# TI_DAC5V.net
KiCad netlist of a schematic drawn in EAGLE
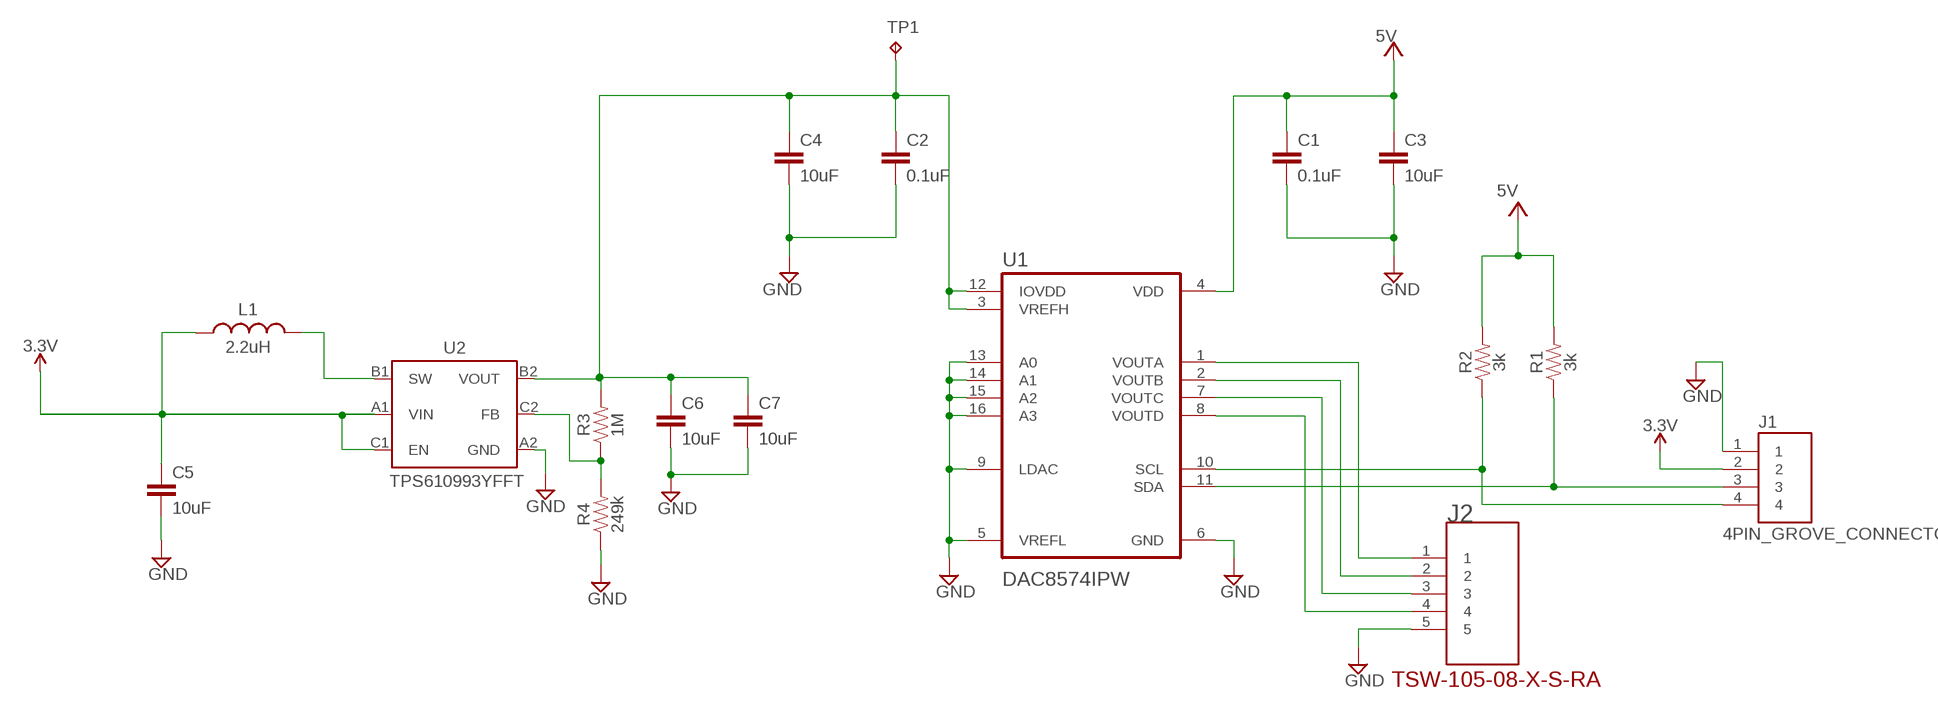
[diagram p0: schematic, sheet 1]

(export (version "E")
  (design (tool "Eeschema 10.0.6"))
  (components
    (comp (ref "C1")
      (value "0.1uF")
      (footprint "eagle-import:1206")
      (libsource (lib "eagle-import") (part "0.1UF-1206"))
    )
    (comp (ref "C2")
      (value "0.1uF")
      (footprint "eagle-import:1206")
      (libsource (lib "eagle-import") (part "0.1UF-1206"))
    )
    (comp (ref "C3")
      (value "10uF")
      (footprint "eagle-import:1206")
      (libsource (lib "eagle-import") (part "10UF-1206"))
    )
    (comp (ref "C4")
      (value "10uF")
      (footprint "eagle-import:1206")
      (libsource (lib "eagle-import") (part "10UF-1206"))
    )
    (comp (ref "C5")
      (value "10uF")
      (footprint "eagle-import:CAPC1608X90N")
      (fields (field (name "MF") "Murata") (field (name "MP") "GRM188R60J106ME47J"))
      (libsource (lib "eagle-import") (part "GRM188R60J106ME47J"))
    )
    (comp (ref "C6")
      (value "10uF")
      (footprint "eagle-import:CAPC1608X90N")
      (fields (field (name "MF") "Murata") (field (name "MP") "GRM188R60J106ME47J"))
      (libsource (lib "eagle-import") (part "GRM188R60J106ME47J"))
    )
    (comp (ref "C7")
      (value "10uF")
      (footprint "eagle-import:CAPC1608X90N")
      (fields (field (name "MF") "Murata") (field (name "MP") "GRM188R60J106ME47J"))
      (libsource (lib "eagle-import") (part "GRM188R60J106ME47J"))
    )
    (comp (ref "J1")
      (value "4PIN_GROVE_CONNECTOR")
      (footprint "eagle-import:SEEED_114020163")
      (fields (field (name "MF") "Seeed Technology Co., Ltd") (field (name "MP") "110990030"))
      (libsource (lib "eagle-import") (part "4PIN_GROVE_CONNECTOR"))
    )
    (comp (ref "J2")
      (value "TSW-105-08-X-S-RAJ")
      (footprint "eagle-import:SAMTEC-TSW-105-08-X-S-RA")
      (fields (field (name "MF") "Samtec") (field (name "MP") "TSW-105-08-T-S-RA"))
      (libsource (lib "eagle-import") (part "TSW-105-08-X-S-RAJ"))
    )
    (comp (ref "L1")
      (value "2.2uH")
      (footprint "eagle-import:VLS201610CX-2R2M-1")
      (libsource (lib "eagle-import") (part "VLS201610CX-2R2M-1"))
    )
    (comp (ref "R1")
      (value "3k")
      (footprint "eagle-import:1206")
      (libsource (lib "eagle-import") (part "3KOHM-1206"))
    )
    (comp (ref "R2")
      (value "3k")
      (footprint "eagle-import:1206")
      (libsource (lib "eagle-import") (part "3KOHM-1206"))
    )
    (comp (ref "R3")
      (value "1M")
      (footprint "eagle-import:0603")
      (libsource (lib "eagle-import") (part "1MOHM"))
    )
    (comp (ref "R4")
      (value "249k")
      (footprint "eagle-import:0603")
      (libsource (lib "eagle-import") (part "249KOHM"))
    )
    (comp (ref "TP1")
      (value "TPPAD1-13")
      (footprint "eagle-import:P1-13")
      (libsource (lib "eagle-import") (part "TPPAD1-13"))
    )
    (comp (ref "U1")
      (value "DAC8574IPW")
      (footprint "eagle-import:SOP65P640X120-16N")
      (fields (field (name "MF") "Texas Instruments"))
      (libsource (lib "eagle-import") (part "DAC8574IPW"))
    )
    (comp (ref "U2")
      (value "TPS610993YFFT")
      (footprint "eagle-import:TPS610993YFFT")
      (libsource (lib "eagle-import") (part "BOOST_CONVERTER"))
    )
  )
  (nets
    (net (code "1") (name "3.3V") (class "Default")
      (node (ref "C5") (pin "1") (pinfunction "1_1") (pintype "passive"))
      (node (ref "J1") (pin "2") (pinfunction "2_2") (pintype "passive"))
      (node (ref "L1") (pin "1") (pinfunction "1_1") (pintype "passive"))
      (node (ref "U2") (pin "A1") (pinfunction "VIN_A1") (pintype "input"))
      (node (ref "U2") (pin "C1") (pinfunction "EN_C1") (pintype "input"))
    )
    (net (code "2") (name "5V") (class "Default")
      (node (ref "C1") (pin "1") (pinfunction "1_1") (pintype "passive"))
      (node (ref "C2") (pin "1") (pinfunction "1_1") (pintype "passive"))
      (node (ref "C3") (pin "1") (pinfunction "1_1") (pintype "passive"))
      (node (ref "C4") (pin "1") (pinfunction "1_1") (pintype "passive"))
      (node (ref "C6") (pin "1") (pinfunction "1_1") (pintype "passive"))
      (node (ref "C7") (pin "1") (pinfunction "1_1") (pintype "passive"))
      (node (ref "R1") (pin "2") (pinfunction "2_2") (pintype "passive"))
      (node (ref "R2") (pin "2") (pinfunction "2_2") (pintype "passive"))
      (node (ref "R3") (pin "2") (pinfunction "2_2") (pintype "passive"))
      (node (ref "TP1") (pin "TP") (pinfunction "TP_TP") (pintype "input"))
      (node (ref "U1") (pin "12") (pinfunction "IOVDD_12") (pintype "power_in"))
      (node (ref "U1") (pin "3") (pinfunction "VREFH_3") (pintype "input"))
      (node (ref "U1") (pin "4") (pinfunction "VDD_4") (pintype "power_in"))
      (node (ref "U2") (pin "B2") (pinfunction "VOUT_B2") (pintype "passive"))
    )
    (net (code "3") (name "GND") (class "Default")
      (node (ref "C1") (pin "2") (pinfunction "2_2") (pintype "passive"))
      (node (ref "C2") (pin "2") (pinfunction "2_2") (pintype "passive"))
      (node (ref "C3") (pin "2") (pinfunction "2_2") (pintype "passive"))
      (node (ref "C4") (pin "2") (pinfunction "2_2") (pintype "passive"))
      (node (ref "C5") (pin "2") (pinfunction "2_2") (pintype "passive"))
      (node (ref "C6") (pin "2") (pinfunction "2_2") (pintype "passive"))
      (node (ref "C7") (pin "2") (pinfunction "2_2") (pintype "passive"))
      (node (ref "J1") (pin "1") (pinfunction "1_1") (pintype "passive"))
      (node (ref "J2") (pin "5") (pinfunction "5_5") (pintype "bidirectional"))
      (node (ref "R4") (pin "1") (pinfunction "1_1") (pintype "passive"))
      (node (ref "U1") (pin "13") (pinfunction "A0_13") (pintype "input"))
      (node (ref "U1") (pin "14") (pinfunction "A1_14") (pintype "input"))
      (node (ref "U1") (pin "15") (pinfunction "A2_15") (pintype "input"))
      (node (ref "U1") (pin "16") (pinfunction "A3_16") (pintype "input"))
      (node (ref "U1") (pin "5") (pinfunction "VREFL_5") (pintype "input"))
      (node (ref "U1") (pin "6") (pinfunction "GND_6") (pintype "power_in"))
      (node (ref "U1") (pin "9") (pinfunction "LDAC_9") (pintype "input"))
      (node (ref "U2") (pin "A2") (pinfunction "GND_A2") (pintype "power_in"))
    )
    (net (code "4") (name "Net-(U1-SCL)") (class "Default")
      (node (ref "J1") (pin "4") (pinfunction "4_4") (pintype "passive"))
      (node (ref "R2") (pin "1") (pinfunction "1_1") (pintype "passive"))
      (node (ref "U1") (pin "10") (pinfunction "SCL_10") (pintype "input"))
    )
    (net (code "5") (name "Net-(U1-SDA)") (class "Default")
      (node (ref "J1") (pin "3") (pinfunction "3_3") (pintype "passive"))
      (node (ref "R1") (pin "1") (pinfunction "1_1") (pintype "passive"))
      (node (ref "U1") (pin "11") (pinfunction "SDA_11") (pintype "input"))
    )
    (net (code "6") (name "Net-(U1-VOUTA)") (class "Default")
      (node (ref "J2") (pin "1") (pinfunction "1_1") (pintype "bidirectional"))
      (node (ref "U1") (pin "1") (pinfunction "VOUTA_1") (pintype "output"))
    )
    (net (code "7") (name "Net-(U1-VOUTB)") (class "Default")
      (node (ref "J2") (pin "2") (pinfunction "2_2") (pintype "bidirectional"))
      (node (ref "U1") (pin "2") (pinfunction "VOUTB_2") (pintype "output"))
    )
    (net (code "8") (name "Net-(U1-VOUTC)") (class "Default")
      (node (ref "J2") (pin "3") (pinfunction "3_3") (pintype "bidirectional"))
      (node (ref "U1") (pin "7") (pinfunction "VOUTC_7") (pintype "output"))
    )
    (net (code "9") (name "Net-(U1-VOUTD)") (class "Default")
      (node (ref "J2") (pin "4") (pinfunction "4_4") (pintype "bidirectional"))
      (node (ref "U1") (pin "8") (pinfunction "VOUTD_8") (pintype "output"))
    )
    (net (code "10") (name "Net-(U2-FB)") (class "Default")
      (node (ref "R3") (pin "1") (pinfunction "1_1") (pintype "passive"))
      (node (ref "R4") (pin "2") (pinfunction "2_2") (pintype "passive"))
      (node (ref "U2") (pin "C2") (pinfunction "FB_C2") (pintype "input"))
    )
    (net (code "11") (name "Net-(U2-SW)") (class "Default")
      (node (ref "L1") (pin "2") (pinfunction "2_2") (pintype "passive"))
      (node (ref "U2") (pin "B1") (pinfunction "SW_B1") (pintype "input"))
    )
  )
)
